# PowerPath.net
KiCad netlist of a schematic drawn in Altium Designer
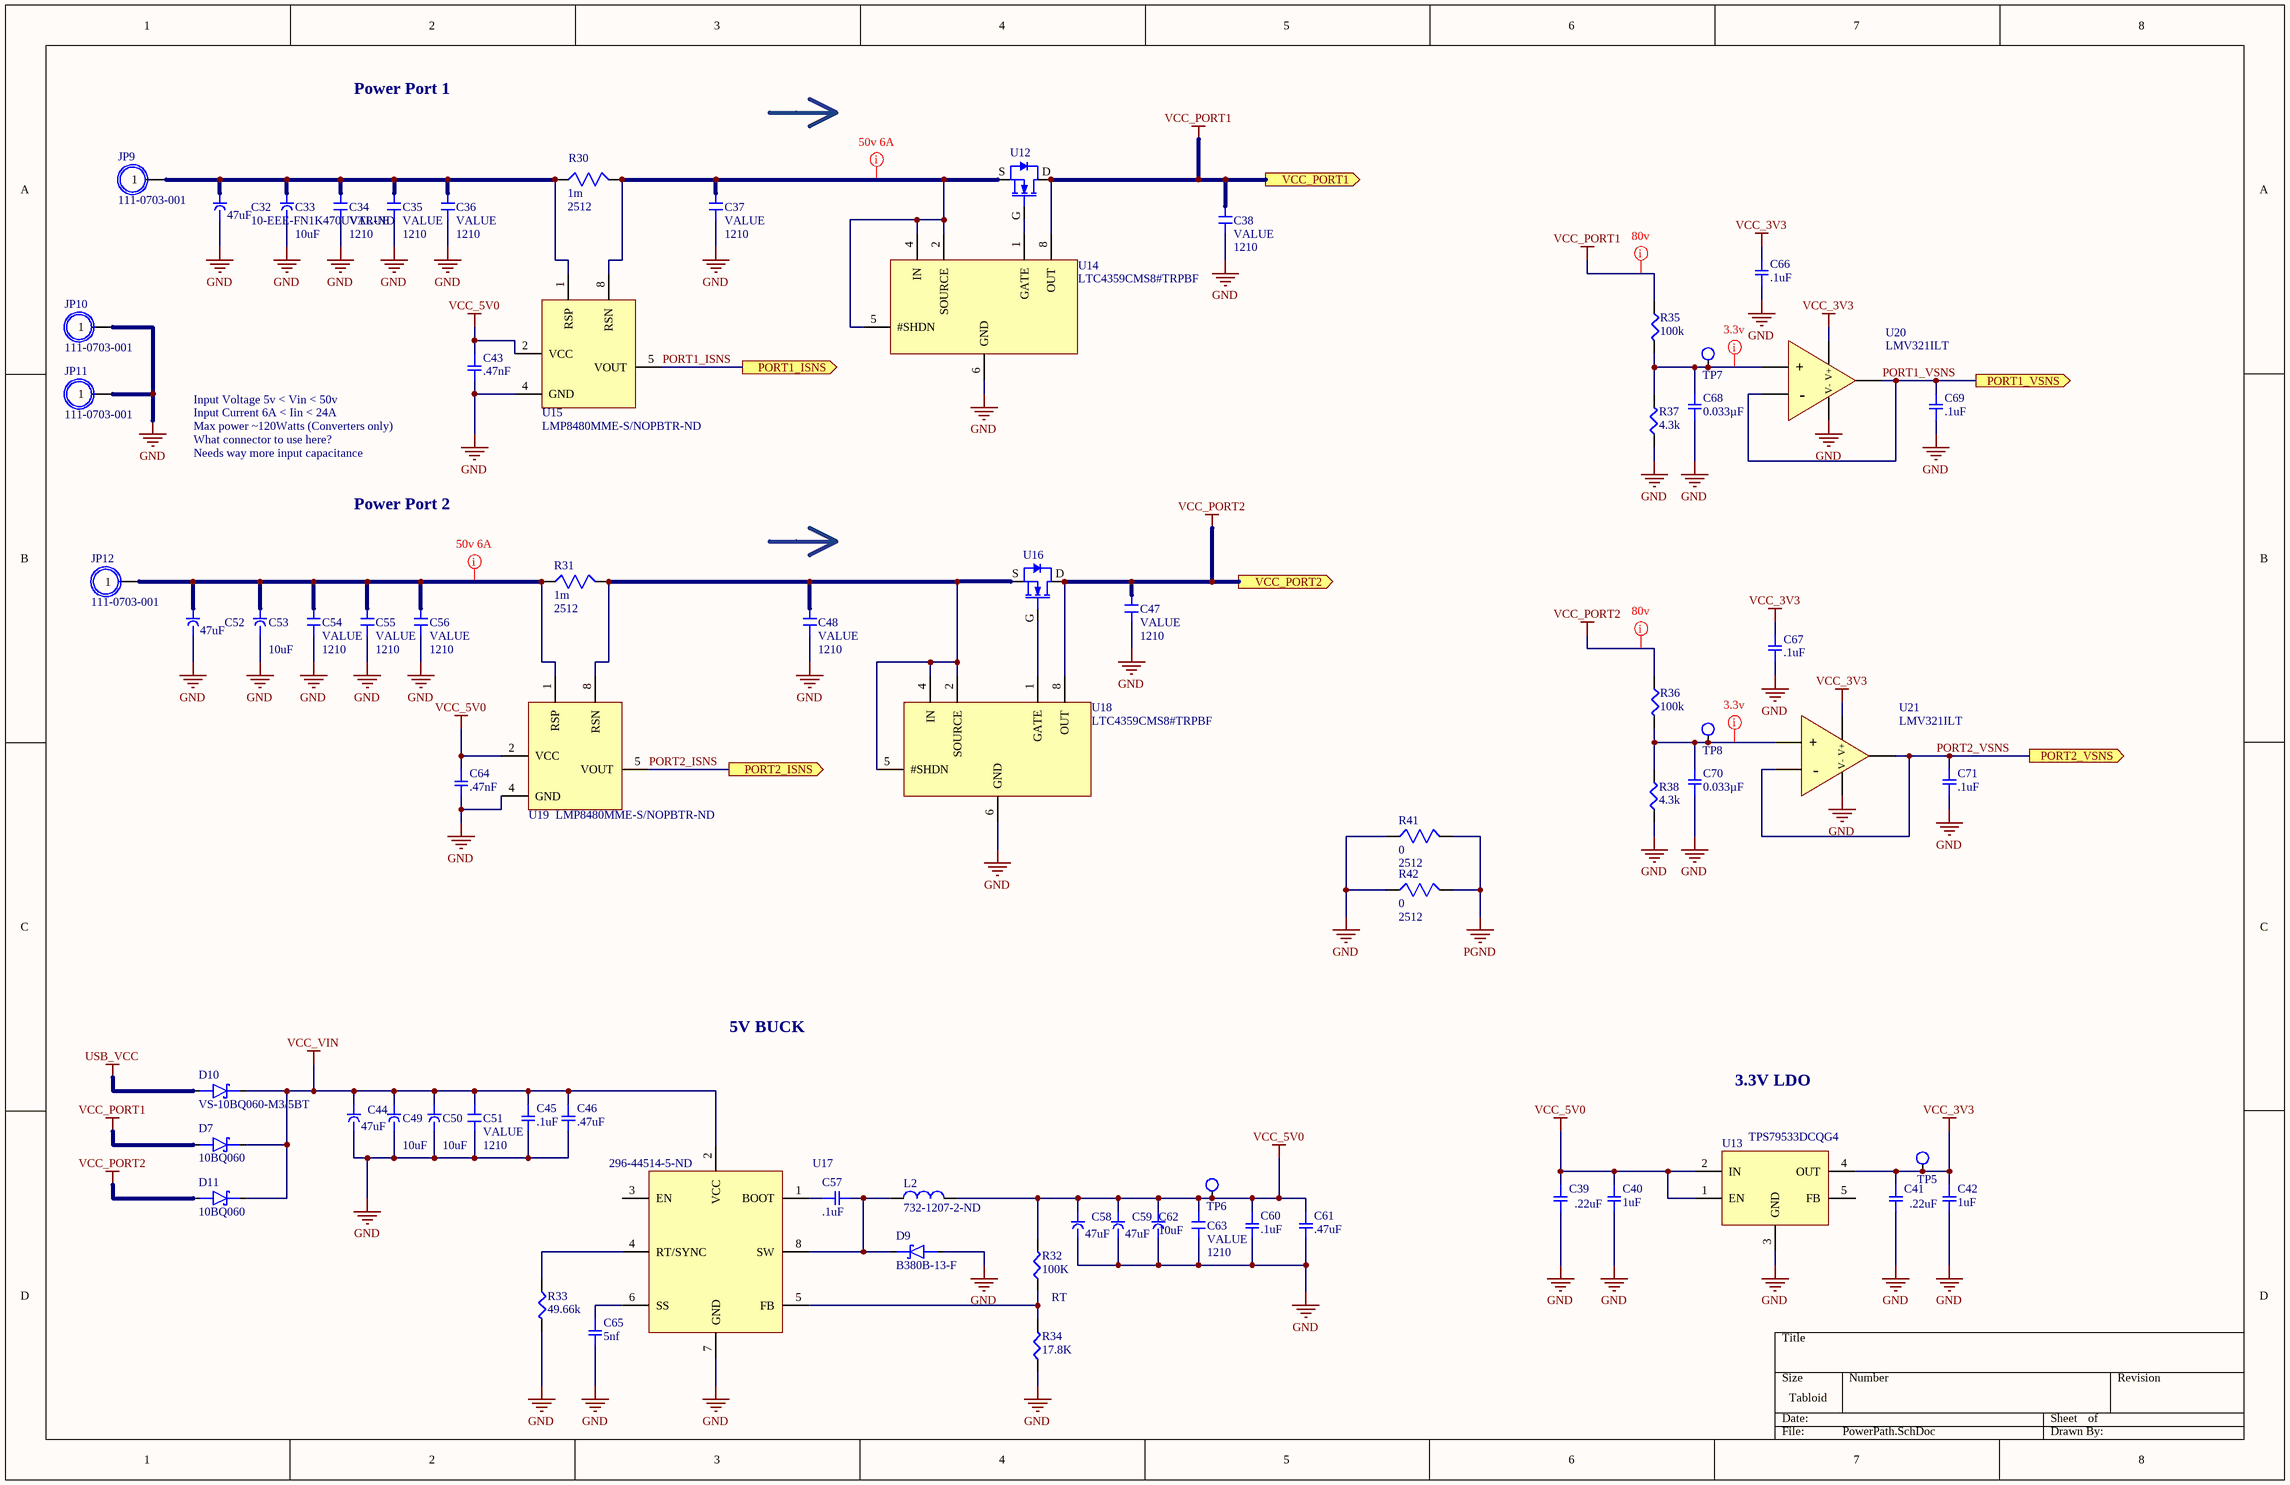
[diagram p0: PowerPath.SchDoc]

(export (version "E")
  (design (tool "Eeschema 10.0.6"))
  (components
    (comp (ref "C32")
      (value "10-EEE-FN1K470UVTR-ND")
      (footprint "EEE-FN1K470UV")
      (description "CAP ALUM 47UF 20% 80V SMD")
      (libsource (lib "UniversalConverter_Symbols") (part "CAP ALUM 47UF"))
    )
    (comp (ref "C33")
      (value "10uF")
      (footprint "panasonic d8")
      (description "CAP ALUM 10UF 20% 80V SMD")
      (fields (field (name "Comment") "EEE-FN1K100XL"))
      (libsource (lib "UniversalConverter_Symbols") (part "CAP ALUM 10UF"))
    )
    (comp (ref "C34")
      (value "VALUE")
      (footprint "1210 cap")
      (description "CAP SMD 1210")
      (fields (field (name "SIZE") "1210"))
      (libsource (lib "UniversalConverter_Symbols") (part "CAP SMD 1210"))
    )
    (comp (ref "C35")
      (value "VALUE")
      (footprint "1210 cap")
      (description "CAP SMD 1210")
      (fields (field (name "SIZE") "1210"))
      (libsource (lib "UniversalConverter_Symbols") (part "CAP SMD 1210"))
    )
    (comp (ref "C36")
      (value "VALUE")
      (footprint "1210 cap")
      (description "CAP SMD 1210")
      (fields (field (name "SIZE") "1210"))
      (libsource (lib "UniversalConverter_Symbols") (part "CAP SMD 1210"))
    )
    (comp (ref "C37")
      (value "VALUE")
      (footprint "1210 cap")
      (description "CAP SMD 1210")
      (fields (field (name "SIZE") "1210"))
      (libsource (lib "UniversalConverter_Symbols") (part "CAP SMD 1210"))
    )
    (comp (ref "C38")
      (value "VALUE")
      (footprint "1210 cap")
      (description "CAP SMD 1210")
      (fields (field (name "SIZE") "1210"))
      (libsource (lib "UniversalConverter_Symbols") (part "CAP SMD 1210"))
    )
    (comp (ref "C39")
      (value ".22uF")
      (footprint "SMD-0603C")
      (description "CAP CER 0.22UF 25V X7R 0603")
      (fields
        (field (name "DIGI-KEY PART NUMBER") "490-5797-1-ND")
        (field (name "PART NUMBER") "GCJ188R71E224KA12D")
      )
      (libsource (lib "capacitor_murata_0603") (part "GCJ188R71E224KA12D"))
    )
    (comp (ref "C40")
      (value "1uF")
      (footprint "SMD-0603C")
      (description "CAP CER 0.22UF 25V X7R 0603")
      (fields
        (field (name "DIGI-KEY PART NUMBER") "490-5797-1-ND")
        (field (name "PART NUMBER") "GCJ188R71E224KA12D")
      )
      (libsource (lib "capacitor_murata_0603") (part "GCJ188R71E224KA12D"))
    )
    (comp (ref "C41")
      (value ".22uF")
      (footprint "SMD-0603C")
      (description "CAP CER 0.22UF 25V X7R 0603")
      (fields
        (field (name "DIGI-KEY PART NUMBER") "490-5797-1-ND")
        (field (name "PART NUMBER") "GCJ188R71E224KA12D")
      )
      (libsource (lib "capacitor_murata_0603") (part "GCJ188R71E224KA12D"))
    )
    (comp (ref "C42")
      (value "1uF")
      (footprint "SMD-0603C")
      (description "CAP CER 0.22UF 25V X7R 0603")
      (fields
        (field (name "DIGI-KEY PART NUMBER") "490-5797-1-ND")
        (field (name "PART NUMBER") "GCJ188R71E224KA12D")
      )
      (libsource (lib "capacitor_murata_0603") (part "GCJ188R71E224KA12D"))
    )
    (comp (ref "C43")
      (value ".47nF")
      (footprint "SMD-0603C")
      (description "CAP CER 2200PF 50V X7R 0603")
      (fields
        (field (name "DIGI-KEY PART NUMBER") "490-5766-1-ND")
        (field (name "PART NUMBER") "GCJ188R71H222KA01D")
      )
      (libsource (lib "capacitor_murata_0603") (part "GCJ188R71H222KA01D"))
    )
    (comp (ref "C44")
      (value "10-EEE-FN1K470UVTR-ND")
      (footprint "EEE-FN1K470UV")
      (description "CAP ALUM 47UF 20% 80V SMD")
      (libsource (lib "UniversalConverter_Symbols") (part "CAP ALUM 47UF"))
    )
    (comp (ref "C45")
      (value ".1uF")
      (footprint "SMD-0805C")
      (description "CAP CER 0.012UF 50V NP0 0805")
      (fields
        (field (name "DIGI-KEY PART NUMBER") "490-12608-1-ND")
        (field (name "PART NUMBER") "GRM2195C1H123FA01D")
      )
      (libsource (lib "capacitor_murata_0805") (part "GRM2195C1H123FA01D"))
    )
    (comp (ref "C46")
      (value ".47uF")
      (footprint "SMD-0805C")
      (description "CAP CER 0.012UF 50V NP0 0805")
      (fields
        (field (name "DIGI-KEY PART NUMBER") "490-12608-1-ND")
        (field (name "PART NUMBER") "GRM2195C1H123FA01D")
      )
      (libsource (lib "capacitor_murata_0805") (part "GRM2195C1H123FA01D"))
    )
    (comp (ref "C47")
      (value "VALUE")
      (footprint "1210 cap")
      (description "CAP SMD 1210")
      (fields (field (name "SIZE") "1210"))
      (libsource (lib "UniversalConverter_Symbols") (part "CAP SMD 1210"))
    )
    (comp (ref "C48")
      (value "VALUE")
      (footprint "1210 cap")
      (description "CAP SMD 1210")
      (fields (field (name "SIZE") "1210"))
      (libsource (lib "UniversalConverter_Symbols") (part "CAP SMD 1210"))
    )
    (comp (ref "C49")
      (value "10uF")
      (footprint "panasonic d8")
      (description "CAP ALUM 10UF 20% 80V SMD")
      (fields (field (name "Comment") "EEE-FN1K100XL"))
      (libsource (lib "UniversalConverter_Symbols") (part "CAP ALUM 10UF"))
    )
    (comp (ref "C50")
      (value "10uF")
      (footprint "panasonic d8")
      (description "CAP ALUM 10UF 20% 80V SMD")
      (fields (field (name "Comment") "EEE-FN1K100XL"))
      (libsource (lib "UniversalConverter_Symbols") (part "CAP ALUM 10UF"))
    )
    (comp (ref "C51")
      (value "VALUE")
      (footprint "1210 cap")
      (description "CAP SMD 1210")
      (fields (field (name "SIZE") "1210"))
      (libsource (lib "UniversalConverter_Symbols") (part "CAP SMD 1210"))
    )
    (comp (ref "C52")
      (value "10-EEE-FN1K470UVTR-ND")
      (footprint "EEE-FN1K470UV")
      (description "CAP ALUM 47UF 20% 80V SMD")
      (libsource (lib "UniversalConverter_Symbols") (part "CAP ALUM 47UF"))
    )
    (comp (ref "C53")
      (value "10uF")
      (footprint "panasonic d8")
      (description "CAP ALUM 10UF 20% 80V SMD")
      (fields (field (name "Comment") "EEE-FN1K100XL"))
      (libsource (lib "UniversalConverter_Symbols") (part "CAP ALUM 10UF"))
    )
    (comp (ref "C54")
      (value "VALUE")
      (footprint "1210 cap")
      (description "CAP SMD 1210")
      (fields (field (name "SIZE") "1210"))
      (libsource (lib "UniversalConverter_Symbols") (part "CAP SMD 1210"))
    )
    (comp (ref "C55")
      (value "VALUE")
      (footprint "1210 cap")
      (description "CAP SMD 1210")
      (fields (field (name "SIZE") "1210"))
      (libsource (lib "UniversalConverter_Symbols") (part "CAP SMD 1210"))
    )
    (comp (ref "C56")
      (value "VALUE")
      (footprint "1210 cap")
      (description "CAP SMD 1210")
      (fields (field (name "SIZE") "1210"))
      (libsource (lib "UniversalConverter_Symbols") (part "CAP SMD 1210"))
    )
    (comp (ref "C57")
      (value ".1uF")
      (footprint "SMD-0805C")
      (description "CAP CER 0.015UF 50V NP0 0805")
      (fields
        (field (name "DIGI-KEY PART NUMBER") "490-11581-1-ND")
        (field (name "PART NUMBER") "GRM2195C1H153GA01D")
      )
      (libsource (lib "capacitor_murata_0805") (part "GRM2195C1H153GA01D"))
    )
    (comp (ref "C58")
      (value "10-EEE-FN1K470UVTR-ND")
      (footprint "EEE-FN1K470UV")
      (description "CAP ALUM 47UF 20% 80V SMD")
      (libsource (lib "UniversalConverter_Symbols") (part "CAP ALUM 47UF"))
    )
    (comp (ref "C59")
      (value "10-EEE-FN1K470UVTR-ND")
      (footprint "EEE-FN1K470UV")
      (description "CAP ALUM 47UF 20% 80V SMD")
      (libsource (lib "UniversalConverter_Symbols") (part "CAP ALUM 47UF"))
    )
    (comp (ref "C60")
      (value ".1uF")
      (footprint "SMD-0805C")
      (description "CAP CER 0.012UF 50V NP0 0805")
      (fields
        (field (name "DIGI-KEY PART NUMBER") "490-12608-1-ND")
        (field (name "PART NUMBER") "GRM2195C1H123FA01D")
      )
      (libsource (lib "capacitor_murata_0805") (part "GRM2195C1H123FA01D"))
    )
    (comp (ref "C61")
      (value ".47uF")
      (footprint "SMD-0805C")
      (description "CAP CER 0.012UF 50V NP0 0805")
      (fields
        (field (name "DIGI-KEY PART NUMBER") "490-12608-1-ND")
        (field (name "PART NUMBER") "GRM2195C1H123FA01D")
      )
      (libsource (lib "capacitor_murata_0805") (part "GRM2195C1H123FA01D"))
    )
    (comp (ref "C62")
      (value "10uF")
      (footprint "panasonic d8")
      (description "CAP ALUM 10UF 20% 80V SMD")
      (fields (field (name "Comment") "EEE-FN1K100XL"))
      (libsource (lib "UniversalConverter_Symbols") (part "CAP ALUM 10UF"))
    )
    (comp (ref "C63")
      (value "VALUE")
      (footprint "1210 cap")
      (description "CAP SMD 1210")
      (fields (field (name "SIZE") "1210"))
      (libsource (lib "UniversalConverter_Symbols") (part "CAP SMD 1210"))
    )
    (comp (ref "C64")
      (value ".47nF")
      (footprint "SMD-0603C")
      (description "CAP CER 2200PF 50V X7R 0603")
      (fields
        (field (name "DIGI-KEY PART NUMBER") "490-5766-1-ND")
        (field (name "PART NUMBER") "GCJ188R71H222KA01D")
      )
      (libsource (lib "capacitor_murata_0603") (part "GCJ188R71H222KA01D"))
    )
    (comp (ref "C65")
      (value "5nf")
      (footprint "SMD-0603C")
      (description "CAP CER 10000PF 100V X7R 0603")
      (fields
        (field (name "DIGI-KEY PART NUMBER") "490-5771-1-ND")
        (field (name "PART NUMBER") "GCJ188R72A103KA01D")
      )
      (libsource (lib "capacitor_murata_0603") (part "GCJ188R72A103KA01D"))
    )
    (comp (ref "C66")
      (value ".1uF")
      (footprint "SMD-0603C")
      (description "CAP CER 0.033UF 50V X7R 0603")
      (fields
        (field (name "DIGI-KEY PART NUMBER") "490-5852-1-ND")
        (field (name "PART NUMBER") "GCJ188R71H333KA12D")
      )
      (libsource (lib "capacitor_murata_0603") (part "GCJ188R71H333KA12D"))
    )
    (comp (ref "C67")
      (value ".1uF")
      (footprint "SMD-0603C")
      (description "CAP CER 0.033UF 50V X7R 0603")
      (fields
        (field (name "DIGI-KEY PART NUMBER") "490-5852-1-ND")
        (field (name "PART NUMBER") "GCJ188R71H333KA12D")
      )
      (libsource (lib "capacitor_murata_0603") (part "GCJ188R71H333KA12D"))
    )
    (comp (ref "C68")
      (value "0.033µF")
      (footprint "SMD-0603C")
      (description "CAP CER 0.033UF 50V X7R 0603")
      (fields
        (field (name "DIGI-KEY PART NUMBER") "490-5852-1-ND")
        (field (name "PART NUMBER") "GCJ188R71H333KA12D")
      )
      (libsource (lib "capacitor_murata_0603") (part "GCJ188R71H333KA12D"))
    )
    (comp (ref "C69")
      (value ".1uF")
      (footprint "SMD-0603C")
      (description "CAP CER 0.033UF 50V X7R 0603")
      (fields
        (field (name "DIGI-KEY PART NUMBER") "490-5852-1-ND")
        (field (name "PART NUMBER") "GCJ188R71H333KA12D")
      )
      (libsource (lib "capacitor_murata_0603") (part "GCJ188R71H333KA12D"))
    )
    (comp (ref "C70")
      (value "0.033µF")
      (footprint "SMD-0603C")
      (description "CAP CER 0.033UF 50V X7R 0603")
      (fields
        (field (name "DIGI-KEY PART NUMBER") "490-5852-1-ND")
        (field (name "PART NUMBER") "GCJ188R71H333KA12D")
      )
      (libsource (lib "capacitor_murata_0603") (part "GCJ188R71H333KA12D"))
    )
    (comp (ref "C71")
      (value ".1uF")
      (footprint "SMD-0603C")
      (description "CAP CER 0.033UF 50V X7R 0603")
      (fields
        (field (name "DIGI-KEY PART NUMBER") "490-5852-1-ND")
        (field (name "PART NUMBER") "GCJ188R71H333KA12D")
      )
      (libsource (lib "capacitor_murata_0603") (part "GCJ188R71H333KA12D"))
    )
    (comp (ref "D7")
      (value "10BQ060")
      (footprint "DO-214AA/SMB")
      (libsource (lib "UniversalConverter_Symbols") (part "DIODE 10BQ060"))
    )
    (comp (ref "D9")
      (value "B380B-13-F")
      (footprint "DO-214AA/SMB")
      (description "DIODE SCHOTTKY 80V 3A SMB")
      (libsource (lib "UniversalConverter_Symbols") (part "DIODE B380B-13-F"))
    )
    (comp (ref "D10")
      (value "VS-10BQ060-M3/5BT")
      (footprint "DO-214AA/SMB")
      (description "DIODE SCHOTTKY 60V 1A SMB")
      (libsource (lib "UniversalConverter_Symbols") (part "DIODE 10BQ060"))
    )
    (comp (ref "D11")
      (value "10BQ060")
      (footprint "DO-214AA/SMB")
      (libsource (lib "UniversalConverter_Symbols") (part "DIODE 10BQ060"))
    )
    (comp (ref "JP9")
      (value "111-0703-001")
      (footprint "Banana Jack Post")
      (description "CONN BIND POST KNURLED BLACK‎")
      (libsource (lib "Personal_Library") (part "CONN BANANA JACK"))
    )
    (comp (ref "JP10")
      (value "111-0703-001")
      (footprint "Banana Jack Post")
      (description "CONN BIND POST KNURLED BLACK‎")
      (libsource (lib "Personal_Library") (part "CONN BANANA JACK"))
    )
    (comp (ref "JP11")
      (value "111-0703-001")
      (footprint "Banana Jack Post")
      (description "CONN BIND POST KNURLED BLACK‎")
      (libsource (lib "Personal_Library") (part "CONN BANANA JACK"))
    )
    (comp (ref "JP12")
      (value "111-0703-001")
      (footprint "Banana Jack Post")
      (description "CONN BIND POST KNURLED BLACK‎")
      (libsource (lib "Personal_Library") (part "CONN BANANA JACK"))
    )
    (comp (ref "L2")
      (value "732-1207-2-ND")
      (footprint "8R2")
      (description "FIXED IND 8.2UH 6.25A 20MOHM SMD")
      (libsource (lib "UniversalConverter_Parts") (part "INDUCTOR 744771008"))
    )
    (comp (ref "R30")
      (value "1m")
      (footprint "2512")
      (description "RES SMD 2512 2W")
      (fields (field (name "SIZE") "2512"))
      (libsource (lib "UniversalConverter_Parts") (part "RES SMD 2512"))
    )
    (comp (ref "R31")
      (value "1m")
      (footprint "2512")
      (description "RES SMD 2512 2W")
      (fields (field (name "SIZE") "2512"))
      (libsource (lib "UniversalConverter_Parts") (part "RES SMD 2512"))
    )
    (comp (ref "R32")
      (value "100K")
      (footprint "SMD-0603-RES")
      (description "RES SMD 0.22 OHM 1% 1/4W 0603")
      (fields (field (name "PART NUMBER") "ERJ-3BQFR22V") (field (name "DIGI-KEY PART NUMBER") "P17245CT-ND"))
      (libsource (lib "Panasonic_ERJ_0603") (part "ERJ-3BQFR22V"))
    )
    (comp (ref "R33")
      (value "49.66k")
      (footprint "SMD-0603-RES")
      (description "RES SMD 0.22 OHM 1% 1/4W 0603")
      (fields (field (name "PART NUMBER") "ERJ-3BQFR22V") (field (name "DIGI-KEY PART NUMBER") "P17245CT-ND"))
      (libsource (lib "Panasonic_ERJ_0603") (part "ERJ-3BQFR22V"))
    )
    (comp (ref "R34")
      (value "17.8K")
      (footprint "SMD-0603-RES")
      (description "RES SMD 0.22 OHM 1% 1/4W 0603")
      (fields (field (name "PART NUMBER") "ERJ-3BQFR22V") (field (name "DIGI-KEY PART NUMBER") "P17245CT-ND"))
      (libsource (lib "Panasonic_ERJ_0603") (part "ERJ-3BQFR22V"))
    )
    (comp (ref "R35")
      (value "100k")
      (footprint "SMD-0805-RES")
      (description "RES SMD 0.011 OHM 1% 1/2W 0805")
      (fields
        (field (name "PART NUMBER") "ERJ-6CWFR011V")
        (field (name "DIGI-KEY PART NUMBER") "P19197CT-ND")
      )
      (libsource (lib "Panasonic_ERJ_0805") (part "ERJ-6CWFR011V"))
    )
    (comp (ref "R36")
      (value "100k")
      (footprint "SMD-0805-RES")
      (description "RES SMD 0.011 OHM 1% 1/2W 0805")
      (fields
        (field (name "PART NUMBER") "ERJ-6CWFR011V")
        (field (name "DIGI-KEY PART NUMBER") "P19197CT-ND")
      )
      (libsource (lib "Panasonic_ERJ_0805") (part "ERJ-6CWFR011V"))
    )
    (comp (ref "R37")
      (value "4.3k")
      (footprint "SMD-0603-RES")
      (description "RES SMD 2 OHM 1% 1/4W 0603")
      (fields (field (name "PART NUMBER") "ERJ-3BQF2R0V") (field (name "DIGI-KEY PART NUMBER") "P17377CT-ND"))
      (libsource (lib "Panasonic_ERJ_0603") (part "ERJ-3BQF2R0V"))
    )
    (comp (ref "R38")
      (value "4.3k")
      (footprint "SMD-0603-RES")
      (description "RES SMD 2 OHM 1% 1/4W 0603")
      (fields (field (name "PART NUMBER") "ERJ-3BQF2R0V") (field (name "DIGI-KEY PART NUMBER") "P17377CT-ND"))
      (libsource (lib "Panasonic_ERJ_0603") (part "ERJ-3BQF2R0V"))
    )
    (comp (ref "R41")
      (value "0")
      (footprint "2512")
      (description "RES SMD 2512 2W")
      (fields (field (name "SIZE") "2512"))
      (libsource (lib "UniversalConverter_Parts") (part "RES SMD 2512"))
    )
    (comp (ref "R42")
      (value "0")
      (footprint "2512")
      (description "RES SMD 2512 2W")
      (fields (field (name "SIZE") "2512"))
      (libsource (lib "UniversalConverter_Parts") (part "RES SMD 2512"))
    )
    (comp (ref "TP5")
      (value "TEST POINT 1MM")
      (footprint "TEST POINT")
      (description "1mm pad for test points")
      (libsource (lib "Personal_Library") (part "TEST POINT 1MM"))
    )
    (comp (ref "TP6")
      (value "TEST POINT 1MM")
      (footprint "TEST POINT")
      (description "1mm pad for test points")
      (libsource (lib "Personal_Library") (part "TEST POINT 1MM"))
    )
    (comp (ref "TP7")
      (value "TEST POINT 1MM")
      (footprint "TEST POINT")
      (description "1mm pad for test points")
      (libsource (lib "Personal_Library") (part "TEST POINT 1MM"))
    )
    (comp (ref "TP8")
      (value "TEST POINT 1MM")
      (footprint "TEST POINT")
      (description "1mm pad for test points")
      (libsource (lib "Personal_Library") (part "TEST POINT 1MM"))
    )
    (comp (ref "U12")
      (value "SQJA80EP-T1_GE3TR-ND")
      (footprint "PowerPAK® SO-8L SINGLE")
      (description "MOSFET N-CH 80V 60A PPAK SO-8")
      (libsource (lib "UniversalConverter_Symbols") (part "FET SQJA80EP-T1_GE3"))
    )
    (comp (ref "U13")
      (value "TPS79533DCQG4")
      (footprint "6 pin sot223")
      (description "IC REG LIN 3.3V 500MA SOT223-6")
      (libsource (lib "UniversalConverter_Parts") (part "IC REG TPS79533DCQG4"))
    )
    (comp (ref "U14")
      (value "LTC4359CMS8#TRPBF")
      (footprint "8-MSOP")
      (description "OR Controller N+1 ORing Controller N-Channel N:1 8-MSOP")
      (libsource (lib "UniversalConverter_Parts") (part "IC LTC4359"))
    )
    (comp (ref "U15")
      (value "LMP8480MME-S/NOPBTR-ND")
      (footprint "DGK(S-PDSO-G8)")
      (description "IC CURR SENSE 1 CIRCUIT 8VSSOP")
      (libsource (lib "UniversalConverter_Parts") (part "IC LMP8480"))
    )
    (comp (ref "U16")
      (value "SQJA80EP-T1_GE3TR-ND")
      (footprint "PowerPAK® SO-8L SINGLE")
      (description "MOSFET N-CH 80V 60A PPAK SO-8")
      (libsource (lib "UniversalConverter_Symbols") (part "FET SQJA80EP-T1_GE3"))
    )
    (comp (ref "U17")
      (value "296-44514-5-ND")
      (footprint "DDA R-PDSO-G8")
      (description "IC REG BUCK ADJUSTABLE 3A 8SOPWR")
      (libsource (lib "UniversalConverter_Symbols") (part "IC LMR16030SDDA"))
    )
    (comp (ref "U18")
      (value "LTC4359CMS8#TRPBF")
      (footprint "8-MSOP")
      (description "OR Controller N+1 ORing Controller N-Channel N:1 8-MSOP")
      (libsource (lib "UniversalConverter_Parts") (part "IC LTC4359"))
    )
    (comp (ref "U19")
      (value "LMP8480MME-S/NOPBTR-ND")
      (footprint "DGK(S-PDSO-G8)")
      (description "IC CURR SENSE 1 CIRCUIT 8VSSOP")
      (libsource (lib "UniversalConverter_Parts") (part "IC LMP8480"))
    )
    (comp (ref "U20")
      (value "LMV321ILT")
      (footprint "SOT-23-5")
      (description "IC OPAMP GP 1 CIRCUIT SOT23-5")
      (libsource (lib "Personal_Library") (part "IC OPAMP GP 1 CIRCUIT"))
    )
    (comp (ref "U21")
      (value "LMV321ILT")
      (footprint "SOT-23-5")
      (description "IC OPAMP GP 1 CIRCUIT SOT23-5")
      (libsource (lib "Personal_Library") (part "IC OPAMP GP 1 CIRCUIT"))
    )
  )
  (nets
    (net (code "1") (name "/PORT1_ISNS") (class "Default")
      (node (ref "U15") (pin "5") (pinfunction "VOUT_5") (pintype "passive"))
    )
    (net (code "2") (name "/PORT1_VSNS") (class "Default")
      (node (ref "C69") (pin "2") (pinfunction "2_2") (pintype "passive"))
      (node (ref "U20") (pin "3") (pinfunction "_-_3") (pintype "passive"))
      (node (ref "U20") (pin "4") (pinfunction "OUT_4") (pintype "passive"))
    )
    (net (code "3") (name "/PORT2_ISNS") (class "Default")
      (node (ref "U19") (pin "5") (pinfunction "VOUT_5") (pintype "passive"))
    )
    (net (code "4") (name "/PORT2_VSNS") (class "Default")
      (node (ref "C71") (pin "2") (pinfunction "2_2") (pintype "passive"))
      (node (ref "U21") (pin "3") (pinfunction "_-_3") (pintype "passive"))
      (node (ref "U21") (pin "4") (pinfunction "OUT_4") (pintype "passive"))
    )
    (net (code "5") (name "GND") (class "Default")
      (node (ref "C32") (pin "1") (pinfunction "1_1") (pintype "passive"))
      (node (ref "C33") (pin "2") (pinfunction "2_2") (pintype "passive"))
      (node (ref "C34") (pin "2") (pinfunction "2_2") (pintype "passive"))
      (node (ref "C35") (pin "2") (pinfunction "2_2") (pintype "passive"))
      (node (ref "C36") (pin "2") (pinfunction "2_2") (pintype "passive"))
      (node (ref "C37") (pin "2") (pinfunction "2_2") (pintype "passive"))
      (node (ref "C38") (pin "2") (pinfunction "2_2") (pintype "passive"))
      (node (ref "C39") (pin "2") (pinfunction "2_2") (pintype "passive"))
      (node (ref "C40") (pin "2") (pinfunction "2_2") (pintype "passive"))
      (node (ref "C41") (pin "2") (pinfunction "2_2") (pintype "passive"))
      (node (ref "C42") (pin "2") (pinfunction "2_2") (pintype "passive"))
      (node (ref "C43") (pin "2") (pinfunction "2_2") (pintype "passive"))
      (node (ref "C44") (pin "1") (pinfunction "1_1") (pintype "passive"))
      (node (ref "C45") (pin "2") (pinfunction "2_2") (pintype "passive"))
      (node (ref "C46") (pin "2") (pinfunction "2_2") (pintype "passive"))
      (node (ref "C47") (pin "2") (pinfunction "2_2") (pintype "passive"))
      (node (ref "C48") (pin "2") (pinfunction "2_2") (pintype "passive"))
      (node (ref "C49") (pin "2") (pinfunction "2_2") (pintype "passive"))
      (node (ref "C50") (pin "2") (pinfunction "2_2") (pintype "passive"))
      (node (ref "C51") (pin "2") (pinfunction "2_2") (pintype "passive"))
      (node (ref "C52") (pin "1") (pinfunction "1_1") (pintype "passive"))
      (node (ref "C53") (pin "2") (pinfunction "2_2") (pintype "passive"))
      (node (ref "C54") (pin "2") (pinfunction "2_2") (pintype "passive"))
      (node (ref "C55") (pin "2") (pinfunction "2_2") (pintype "passive"))
      (node (ref "C56") (pin "2") (pinfunction "2_2") (pintype "passive"))
      (node (ref "C58") (pin "1") (pinfunction "1_1") (pintype "passive"))
      (node (ref "C59") (pin "1") (pinfunction "1_1") (pintype "passive"))
      (node (ref "C60") (pin "2") (pinfunction "2_2") (pintype "passive"))
      (node (ref "C61") (pin "2") (pinfunction "2_2") (pintype "passive"))
      (node (ref "C62") (pin "2") (pinfunction "2_2") (pintype "passive"))
      (node (ref "C63") (pin "2") (pinfunction "2_2") (pintype "passive"))
      (node (ref "C64") (pin "2") (pinfunction "2_2") (pintype "passive"))
      (node (ref "C65") (pin "2") (pinfunction "2_2") (pintype "passive"))
      (node (ref "C66") (pin "1") (pinfunction "1_1") (pintype "passive"))
      (node (ref "C67") (pin "1") (pinfunction "1_1") (pintype "passive"))
      (node (ref "C68") (pin "1") (pinfunction "1_1") (pintype "passive"))
      (node (ref "C69") (pin "1") (pinfunction "1_1") (pintype "passive"))
      (node (ref "C70") (pin "1") (pinfunction "1_1") (pintype "passive"))
      (node (ref "C71") (pin "1") (pinfunction "1_1") (pintype "passive"))
      (node (ref "D9") (pin "2") (pinfunction "2_2") (pintype "passive"))
      (node (ref "JP10") (pin "1") (pinfunction "1_1") (pintype "passive"))
      (node (ref "JP11") (pin "1") (pinfunction "1_1") (pintype "passive"))
      (node (ref "R33") (pin "2") (pinfunction "2_2") (pintype "passive"))
      (node (ref "R34") (pin "1") (pinfunction "1_1") (pintype "passive"))
      (node (ref "R37") (pin "1") (pinfunction "1_1") (pintype "passive"))
      (node (ref "R38") (pin "1") (pinfunction "1_1") (pintype "passive"))
      (node (ref "R41") (pin "1") (pinfunction "1_1") (pintype "passive"))
      (node (ref "R42") (pin "1") (pinfunction "1_1") (pintype "passive"))
      (node (ref "U13") (pin "3") (pinfunction "GND_3") (pintype "passive"))
      (node (ref "U14") (pin "6") (pinfunction "GND_6") (pintype "passive"))
      (node (ref "U15") (pin "4") (pinfunction "GND_4") (pintype "passive"))
      (node (ref "U17") (pin "7") (pinfunction "GND_7") (pintype "passive"))
      (node (ref "U18") (pin "6") (pinfunction "GND_6") (pintype "passive"))
      (node (ref "U19") (pin "4") (pinfunction "GND_4") (pintype "passive"))
      (node (ref "U20") (pin "2") (pinfunction "V-_2") (pintype "passive"))
      (node (ref "U21") (pin "2") (pinfunction "V-_2") (pintype "passive"))
    )
    (net (code "6") (name "Net-(U12-GATE)") (class "Default")
      (node (ref "U12") (pin "G") (pinfunction "GATE_G") (pintype "passive"))
      (node (ref "U14") (pin "1") (pinfunction "GATE_1") (pintype "passive"))
    )
    (net (code "7") (name "Net-(U12-SOURCE)") (class "Default")
      (node (ref "C37") (pin "1") (pinfunction "1_1") (pintype "passive"))
      (node (ref "R30") (pin "2") (pinfunction "2_2") (pintype "passive"))
      (node (ref "U12") (pin "S") (pinfunction "SOURCE_S") (pintype "passive"))
      (node (ref "U14") (pin "2") (pinfunction "SOURCE_2") (pintype "passive"))
      (node (ref "U14") (pin "4") (pinfunction "IN_4") (pintype "passive"))
      (node (ref "U14") (pin "5") (pinfunction "#SHDN_5") (pintype "passive"))
      (node (ref "U15") (pin "8") (pinfunction "RSN_8") (pintype "passive"))
    )
    (net (code "8") (name "Net-(U15-RSP)") (class "Default")
      (node (ref "C32") (pin "2") (pinfunction "2_2") (pintype "passive"))
      (node (ref "C33") (pin "1") (pinfunction "1_1") (pintype "passive"))
      (node (ref "C34") (pin "1") (pinfunction "1_1") (pintype "passive"))
      (node (ref "C35") (pin "1") (pinfunction "1_1") (pintype "passive"))
      (node (ref "C36") (pin "1") (pinfunction "1_1") (pintype "passive"))
      (node (ref "JP9") (pin "1") (pinfunction "1_1") (pintype "passive"))
      (node (ref "R30") (pin "1") (pinfunction "1_1") (pintype "passive"))
      (node (ref "U15") (pin "1") (pinfunction "RSP_1") (pintype "passive"))
    )
    (net (code "9") (name "Net-(U16-GATE)") (class "Default")
      (node (ref "U16") (pin "G") (pinfunction "GATE_G") (pintype "passive"))
      (node (ref "U18") (pin "1") (pinfunction "GATE_1") (pintype "passive"))
    )
    (net (code "10") (name "Net-(U16-SOURCE)") (class "Default")
      (node (ref "C48") (pin "1") (pinfunction "1_1") (pintype "passive"))
      (node (ref "R31") (pin "2") (pinfunction "2_2") (pintype "passive"))
      (node (ref "U16") (pin "S") (pinfunction "SOURCE_S") (pintype "passive"))
      (node (ref "U18") (pin "2") (pinfunction "SOURCE_2") (pintype "passive"))
      (node (ref "U18") (pin "4") (pinfunction "IN_4") (pintype "passive"))
      (node (ref "U18") (pin "5") (pinfunction "#SHDN_5") (pintype "passive"))
      (node (ref "U19") (pin "8") (pinfunction "RSN_8") (pintype "passive"))
    )
    (net (code "11") (name "Net-(U17-BOOT)") (class "Default")
      (node (ref "C57") (pin "1") (pinfunction "1_1") (pintype "passive"))
      (node (ref "U17") (pin "1") (pinfunction "BOOT_1") (pintype "passive"))
    )
    (net (code "12") (name "Net-(U17-FB)") (class "Default")
      (node (ref "R32") (pin "1") (pinfunction "1_1") (pintype "passive"))
      (node (ref "R34") (pin "2") (pinfunction "2_2") (pintype "passive"))
      (node (ref "U17") (pin "5") (pinfunction "FB_5") (pintype "passive"))
    )
    (net (code "13") (name "Net-(U17-RT{slash}SYNC)") (class "Default")
      (node (ref "R33") (pin "1") (pinfunction "1_1") (pintype "passive"))
      (node (ref "U17") (pin "4") (pinfunction "RT/SYNC_4") (pintype "passive"))
    )
    (net (code "14") (name "Net-(U17-SS)") (class "Default")
      (node (ref "C65") (pin "1") (pinfunction "1_1") (pintype "passive"))
      (node (ref "U17") (pin "6") (pinfunction "SS_6") (pintype "passive"))
    )
    (net (code "15") (name "Net-(U17-SW)") (class "Default")
      (node (ref "C57") (pin "2") (pinfunction "2_2") (pintype "passive"))
      (node (ref "D9") (pin "1") (pinfunction "1_1") (pintype "passive"))
      (node (ref "L2") (pin "1") (pinfunction "1_1") (pintype "passive"))
      (node (ref "U17") (pin "8") (pinfunction "SW_8") (pintype "passive"))
    )
    (net (code "16") (name "Net-(U19-RSP)") (class "Default")
      (node (ref "C52") (pin "2") (pinfunction "2_2") (pintype "passive"))
      (node (ref "C53") (pin "1") (pinfunction "1_1") (pintype "passive"))
      (node (ref "C54") (pin "1") (pinfunction "1_1") (pintype "passive"))
      (node (ref "C55") (pin "1") (pinfunction "1_1") (pintype "passive"))
      (node (ref "C56") (pin "1") (pinfunction "1_1") (pintype "passive"))
      (node (ref "JP12") (pin "1") (pinfunction "1_1") (pintype "passive"))
      (node (ref "R31") (pin "1") (pinfunction "1_1") (pintype "passive"))
      (node (ref "U19") (pin "1") (pinfunction "RSP_1") (pintype "passive"))
    )
    (net (code "17") (name "Net-(U20-+)") (class "Default")
      (node (ref "C68") (pin "2") (pinfunction "2_2") (pintype "passive"))
      (node (ref "R35") (pin "2") (pinfunction "2_2") (pintype "passive"))
      (node (ref "R37") (pin "2") (pinfunction "2_2") (pintype "passive"))
      (node (ref "TP7") (pin "1") (pinfunction "1_1") (pintype "passive"))
      (node (ref "U20") (pin "1") (pinfunction "+_1") (pintype "passive"))
    )
    (net (code "18") (name "Net-(U21-+)") (class "Default")
      (node (ref "C70") (pin "2") (pinfunction "2_2") (pintype "passive"))
      (node (ref "R36") (pin "2") (pinfunction "2_2") (pintype "passive"))
      (node (ref "R38") (pin "2") (pinfunction "2_2") (pintype "passive"))
      (node (ref "TP8") (pin "1") (pinfunction "1_1") (pintype "passive"))
      (node (ref "U21") (pin "1") (pinfunction "+_1") (pintype "passive"))
    )
    (net (code "19") (name "PGND") (class "Default")
      (node (ref "R41") (pin "2") (pinfunction "2_2") (pintype "passive"))
      (node (ref "R42") (pin "2") (pinfunction "2_2") (pintype "passive"))
    )
    (net (code "20") (name "USB_VCC") (class "Default")
      (node (ref "D10") (pin "2") (pinfunction "2_2") (pintype "passive"))
    )
    (net (code "21") (name "VCC_3V3") (class "Default")
      (node (ref "C41") (pin "1") (pinfunction "1_1") (pintype "passive"))
      (node (ref "C42") (pin "1") (pinfunction "1_1") (pintype "passive"))
      (node (ref "C66") (pin "2") (pinfunction "2_2") (pintype "passive"))
      (node (ref "C67") (pin "2") (pinfunction "2_2") (pintype "passive"))
      (node (ref "TP5") (pin "1") (pinfunction "1_1") (pintype "passive"))
      (node (ref "U13") (pin "4") (pinfunction "OUT_4") (pintype "passive"))
      (node (ref "U20") (pin "5") (pinfunction "V+_5") (pintype "passive"))
      (node (ref "U21") (pin "5") (pinfunction "V+_5") (pintype "passive"))
    )
    (net (code "22") (name "VCC_5V0") (class "Default")
      (node (ref "C39") (pin "1") (pinfunction "1_1") (pintype "passive"))
      (node (ref "C40") (pin "1") (pinfunction "1_1") (pintype "passive"))
      (node (ref "C43") (pin "1") (pinfunction "1_1") (pintype "passive"))
      (node (ref "C58") (pin "2") (pinfunction "2_2") (pintype "passive"))
      (node (ref "C59") (pin "2") (pinfunction "2_2") (pintype "passive"))
      (node (ref "C60") (pin "1") (pinfunction "1_1") (pintype "passive"))
      (node (ref "C61") (pin "1") (pinfunction "1_1") (pintype "passive"))
      (node (ref "C62") (pin "1") (pinfunction "1_1") (pintype "passive"))
      (node (ref "C63") (pin "1") (pinfunction "1_1") (pintype "passive"))
      (node (ref "C64") (pin "1") (pinfunction "1_1") (pintype "passive"))
      (node (ref "L2") (pin "2") (pinfunction "2_2") (pintype "passive"))
      (node (ref "R32") (pin "2") (pinfunction "2_2") (pintype "passive"))
      (node (ref "TP6") (pin "1") (pinfunction "1_1") (pintype "passive"))
      (node (ref "U13") (pin "1") (pinfunction "EN_1") (pintype "passive"))
      (node (ref "U13") (pin "2") (pinfunction "IN_2") (pintype "passive"))
      (node (ref "U15") (pin "2") (pinfunction "VCC_2") (pintype "passive"))
      (node (ref "U19") (pin "2") (pinfunction "VCC_2") (pintype "passive"))
    )
    (net (code "23") (name "VCC_PORT1") (class "Default")
      (node (ref "C38") (pin "1") (pinfunction "1_1") (pintype "passive"))
      (node (ref "D7") (pin "2") (pinfunction "2_2") (pintype "passive"))
      (node (ref "R35") (pin "1") (pinfunction "1_1") (pintype "passive"))
      (node (ref "U12") (pin "D") (pinfunction "DRAIN_D") (pintype "passive"))
      (node (ref "U14") (pin "8") (pinfunction "OUT_8") (pintype "passive"))
    )
    (net (code "24") (name "VCC_PORT2") (class "Default")
      (node (ref "C47") (pin "1") (pinfunction "1_1") (pintype "passive"))
      (node (ref "D11") (pin "2") (pinfunction "2_2") (pintype "passive"))
      (node (ref "R36") (pin "1") (pinfunction "1_1") (pintype "passive"))
      (node (ref "U16") (pin "D") (pinfunction "DRAIN_D") (pintype "passive"))
      (node (ref "U18") (pin "8") (pinfunction "OUT_8") (pintype "passive"))
    )
    (net (code "25") (name "VCC_VIN") (class "Default")
      (node (ref "C44") (pin "2") (pinfunction "2_2") (pintype "passive"))
      (node (ref "C45") (pin "1") (pinfunction "1_1") (pintype "passive"))
      (node (ref "C46") (pin "1") (pinfunction "1_1") (pintype "passive"))
      (node (ref "C49") (pin "1") (pinfunction "1_1") (pintype "passive"))
      (node (ref "C50") (pin "1") (pinfunction "1_1") (pintype "passive"))
      (node (ref "C51") (pin "1") (pinfunction "1_1") (pintype "passive"))
      (node (ref "D10") (pin "1") (pinfunction "1_1") (pintype "passive"))
      (node (ref "D11") (pin "1") (pinfunction "1_1") (pintype "passive"))
      (node (ref "D7") (pin "1") (pinfunction "1_1") (pintype "passive"))
      (node (ref "U17") (pin "2") (pinfunction "VCC_2") (pintype "passive"))
    )
    (net (code "26") (name "unconnected-(U13-FB-Pad5)") (class "Default")
      (node (ref "U13") (pin "5") (pinfunction "FB_5") (pintype "passive"))
    )
    (net (code "27") (name "unconnected-(U17-EN-Pad3)") (class "Default")
      (node (ref "U17") (pin "3") (pinfunction "EN_3") (pintype "passive"))
    )
  )
)
